# circuit.net
KiCad netlist of a schematic drawn in EAGLE
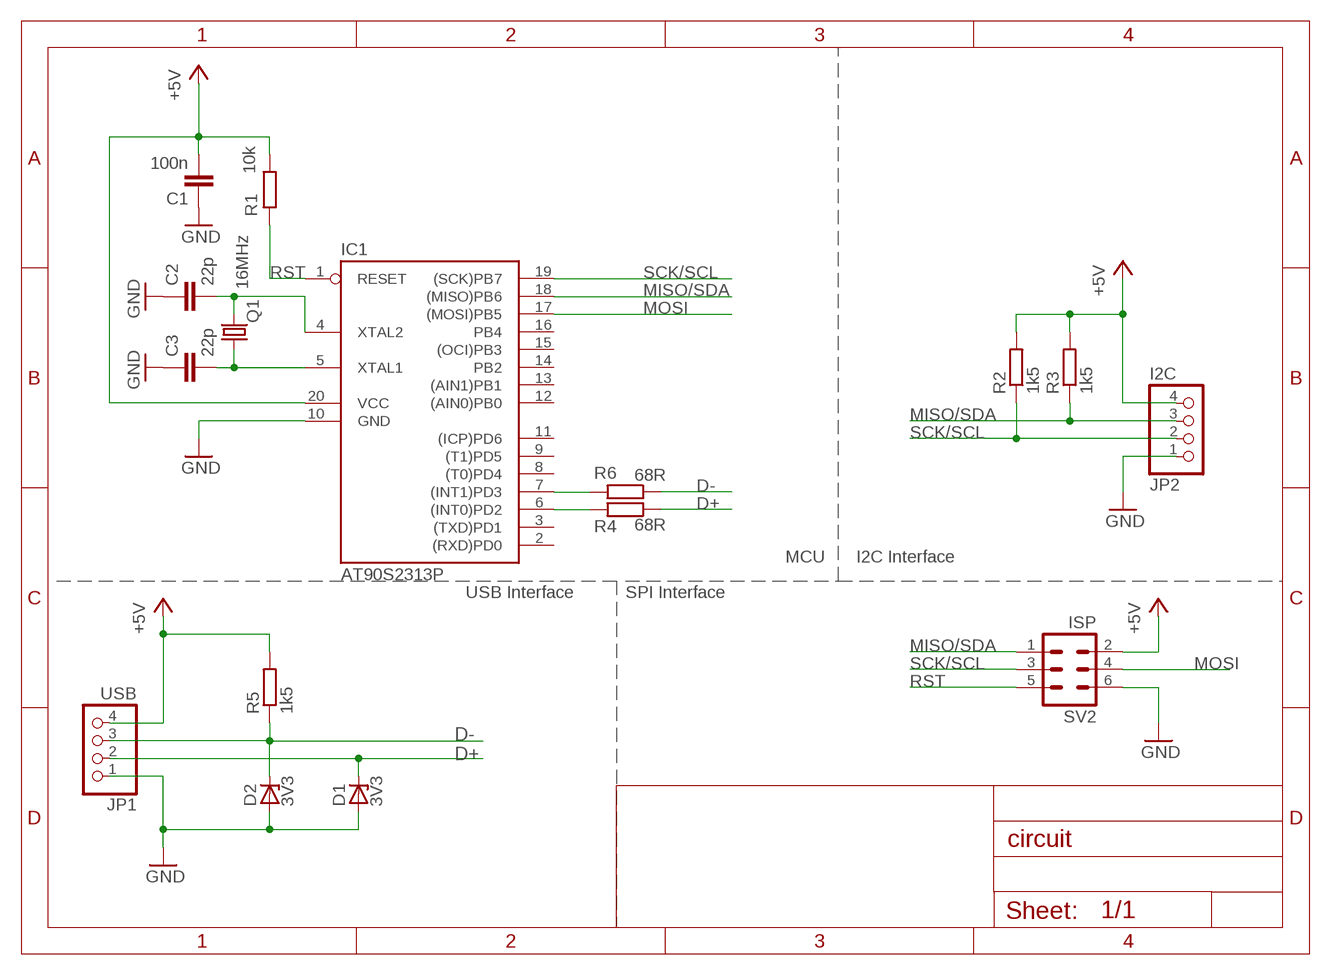
[diagram p0: schematic, sheet 1]

(export (version "E")
  (design (tool "Eeschema 10.0.6"))
  (components
    (comp (ref "C1")
      (value "100n")
      (footprint "eagle-import:C0805")
      (libsource (lib "eagle-import") (part "C-EUC0805"))
    )
    (comp (ref "C2")
      (value "22p")
      (footprint "eagle-import:C0805")
      (libsource (lib "eagle-import") (part "C-EUC0805"))
    )
    (comp (ref "C3")
      (value "22p")
      (footprint "eagle-import:C0805")
      (libsource (lib "eagle-import") (part "C-EUC0805"))
    )
    (comp (ref "D1")
      (value "3V3")
      (footprint "eagle-import:DO34Z7")
      (libsource (lib "eagle-import") (part "ZENER-DIODEDO34-7"))
    )
    (comp (ref "D2")
      (value "3V3")
      (footprint "eagle-import:DO34Z7")
      (libsource (lib "eagle-import") (part "ZENER-DIODEDO34-7"))
    )
    (comp (ref "IC1")
      (value "AT90S2313P")
      (footprint "eagle-import:DIL20")
      (libsource (lib "eagle-import") (part "AT90S2313P"))
    )
    (comp (ref "JP1")
      (value "USB")
      (footprint "eagle-import:1X04")
      (libsource (lib "eagle-import") (part "PINHD-1X4"))
    )
    (comp (ref "JP2")
      (value "I2C")
      (footprint "eagle-import:1X04")
      (libsource (lib "eagle-import") (part "PINHD-1X4"))
    )
    (comp (ref "Q1")
      (value "16MHz")
      (footprint "eagle-import:HC49_S")
      (libsource (lib "eagle-import") (part "CRYTALHC49S"))
    )
    (comp (ref "R1")
      (value "10k")
      (footprint "eagle-import:0207_10")
      (libsource (lib "eagle-import") (part "R-EU_0207/10"))
    )
    (comp (ref "R2")
      (value "1k5")
      (footprint "eagle-import:0207_10")
      (libsource (lib "eagle-import") (part "R-EU_0207/10"))
    )
    (comp (ref "R3")
      (value "1k5")
      (footprint "eagle-import:0207_10")
      (libsource (lib "eagle-import") (part "R-EU_0207/10"))
    )
    (comp (ref "R4")
      (value "68R")
      (footprint "eagle-import:0207_10")
      (libsource (lib "eagle-import") (part "R-EU_0207/10"))
    )
    (comp (ref "R5")
      (value "1k5")
      (footprint "eagle-import:0207_10")
      (libsource (lib "eagle-import") (part "R-EU_0207/10"))
    )
    (comp (ref "R6")
      (value "68R")
      (footprint "eagle-import:0207_10")
      (libsource (lib "eagle-import") (part "R-EU_0207/10"))
    )
    (comp (ref "SV2")
      (value "ISP")
      (footprint "eagle-import:ML6")
      (libsource (lib "eagle-import") (part "ML6"))
    )
  )
  (nets
    (net (code "1") (name "+5V") (class "Default")
      (node (ref "C1") (pin "2") (pinfunction "2_2") (pintype "passive"))
      (node (ref "IC1") (pin "20") (pinfunction "VCC_20") (pintype "power_in"))
      (node (ref "JP1") (pin "4") (pinfunction "4_4") (pintype "passive"))
      (node (ref "JP2") (pin "4") (pinfunction "4_4") (pintype "passive"))
      (node (ref "R1") (pin "2") (pinfunction "2_2") (pintype "passive"))
      (node (ref "R2") (pin "2") (pinfunction "2_2") (pintype "passive"))
      (node (ref "R3") (pin "2") (pinfunction "2_2") (pintype "passive"))
      (node (ref "R5") (pin "2") (pinfunction "2_2") (pintype "passive"))
      (node (ref "SV2") (pin "2") (pinfunction "2_2") (pintype "passive"))
    )
    (net (code "2") (name "/D+") (class "Default")
      (node (ref "D1") (pin "C") (pinfunction "C_C") (pintype "passive"))
      (node (ref "JP1") (pin "2") (pinfunction "2_2") (pintype "passive"))
      (node (ref "R4") (pin "1") (pinfunction "1_1") (pintype "passive"))
    )
    (net (code "3") (name "/D-") (class "Default")
      (node (ref "D2") (pin "C") (pinfunction "C_C") (pintype "passive"))
      (node (ref "JP1") (pin "3") (pinfunction "3_3") (pintype "passive"))
      (node (ref "R5") (pin "1") (pinfunction "1_1") (pintype "passive"))
      (node (ref "R6") (pin "1") (pinfunction "1_1") (pintype "passive"))
    )
    (net (code "4") (name "/MISO{slash}SDA") (class "Default")
      (node (ref "IC1") (pin "18") (pinfunction "(MISO)PB6_18") (pintype "bidirectional"))
      (node (ref "JP2") (pin "3") (pinfunction "3_3") (pintype "passive"))
      (node (ref "R3") (pin "1") (pinfunction "1_1") (pintype "passive"))
      (node (ref "SV2") (pin "1") (pinfunction "1_1") (pintype "passive"))
    )
    (net (code "5") (name "/MOSI") (class "Default")
      (node (ref "IC1") (pin "17") (pinfunction "(MOSI)PB5_17") (pintype "bidirectional"))
      (node (ref "SV2") (pin "4") (pinfunction "4_4") (pintype "passive"))
    )
    (net (code "6") (name "/RST") (class "Default")
      (node (ref "IC1") (pin "1") (pinfunction "RESET_1") (pintype "bidirectional"))
      (node (ref "R1") (pin "1") (pinfunction "1_1") (pintype "passive"))
      (node (ref "SV2") (pin "5") (pinfunction "5_5") (pintype "passive"))
    )
    (net (code "7") (name "/SCK{slash}SCL") (class "Default")
      (node (ref "IC1") (pin "19") (pinfunction "(SCK)PB7_19") (pintype "bidirectional"))
      (node (ref "JP2") (pin "2") (pinfunction "2_2") (pintype "passive"))
      (node (ref "R2") (pin "1") (pinfunction "1_1") (pintype "passive"))
      (node (ref "SV2") (pin "3") (pinfunction "3_3") (pintype "passive"))
    )
    (net (code "8") (name "GND") (class "Default")
      (node (ref "C1") (pin "1") (pinfunction "1_1") (pintype "passive"))
      (node (ref "C2") (pin "1") (pinfunction "1_1") (pintype "passive"))
      (node (ref "C3") (pin "1") (pinfunction "1_1") (pintype "passive"))
      (node (ref "D1") (pin "A") (pinfunction "A_A") (pintype "passive"))
      (node (ref "D2") (pin "A") (pinfunction "A_A") (pintype "passive"))
      (node (ref "IC1") (pin "10") (pinfunction "GND_10") (pintype "power_in"))
      (node (ref "JP1") (pin "1") (pinfunction "1_1") (pintype "passive"))
      (node (ref "JP2") (pin "1") (pinfunction "1_1") (pintype "passive"))
      (node (ref "SV2") (pin "6") (pinfunction "6_6") (pintype "passive"))
    )
    (net (code "9") (name "Net-(IC1-(INT0)PD2)") (class "Default")
      (node (ref "IC1") (pin "6") (pinfunction "(INT0)PD2_6") (pintype "bidirectional"))
      (node (ref "R4") (pin "2") (pinfunction "2_2") (pintype "passive"))
    )
    (net (code "10") (name "Net-(IC1-(INT1)PD3)") (class "Default")
      (node (ref "IC1") (pin "7") (pinfunction "(INT1)PD3_7") (pintype "bidirectional"))
      (node (ref "R6") (pin "2") (pinfunction "2_2") (pintype "passive"))
    )
    (net (code "11") (name "Net-(IC1-XTAL1)") (class "Default")
      (node (ref "C3") (pin "2") (pinfunction "2_2") (pintype "passive"))
      (node (ref "IC1") (pin "5") (pinfunction "XTAL1_5") (pintype "bidirectional"))
      (node (ref "Q1") (pin "1") (pinfunction "1_1") (pintype "passive"))
    )
    (net (code "12") (name "Net-(IC1-XTAL2)") (class "Default")
      (node (ref "C2") (pin "2") (pinfunction "2_2") (pintype "passive"))
      (node (ref "IC1") (pin "4") (pinfunction "XTAL2_4") (pintype "bidirectional"))
      (node (ref "Q1") (pin "2") (pinfunction "2_2") (pintype "passive"))
    )
    (net (code "13") (name "unconnected-(IC1-(AIN0)PB0-Pad12)") (class "Default")
      (node (ref "IC1") (pin "12") (pinfunction "(AIN0)PB0_12") (pintype "bidirectional"))
    )
    (net (code "14") (name "unconnected-(IC1-(AIN1)PB1-Pad13)") (class "Default")
      (node (ref "IC1") (pin "13") (pinfunction "(AIN1)PB1_13") (pintype "bidirectional"))
    )
    (net (code "15") (name "unconnected-(IC1-(ICP)PD6-Pad11)") (class "Default")
      (node (ref "IC1") (pin "11") (pinfunction "(ICP)PD6_11") (pintype "bidirectional"))
    )
    (net (code "16") (name "unconnected-(IC1-(OCI)PB3-Pad15)") (class "Default")
      (node (ref "IC1") (pin "15") (pinfunction "(OCI)PB3_15") (pintype "bidirectional"))
    )
    (net (code "17") (name "unconnected-(IC1-(RXD)PD0-Pad2)") (class "Default")
      (node (ref "IC1") (pin "2") (pinfunction "(RXD)PD0_2") (pintype "bidirectional"))
    )
    (net (code "18") (name "unconnected-(IC1-(T0)PD4-Pad8)") (class "Default")
      (node (ref "IC1") (pin "8") (pinfunction "(T0)PD4_8") (pintype "bidirectional"))
    )
    (net (code "19") (name "unconnected-(IC1-(T1)PD5-Pad9)") (class "Default")
      (node (ref "IC1") (pin "9") (pinfunction "(T1)PD5_9") (pintype "bidirectional"))
    )
    (net (code "20") (name "unconnected-(IC1-(TXD)PD1-Pad3)") (class "Default")
      (node (ref "IC1") (pin "3") (pinfunction "(TXD)PD1_3") (pintype "bidirectional"))
    )
    (net (code "21") (name "unconnected-(IC1-PB2-Pad14)") (class "Default")
      (node (ref "IC1") (pin "14") (pinfunction "PB2_14") (pintype "bidirectional"))
    )
    (net (code "22") (name "unconnected-(IC1-PB4-Pad16)") (class "Default")
      (node (ref "IC1") (pin "16") (pinfunction "PB4_16") (pintype "bidirectional"))
    )
  )
)
